# 150226_AriloRX_REV2_0_0.net
KiCad netlist of a schematic drawn in EAGLE
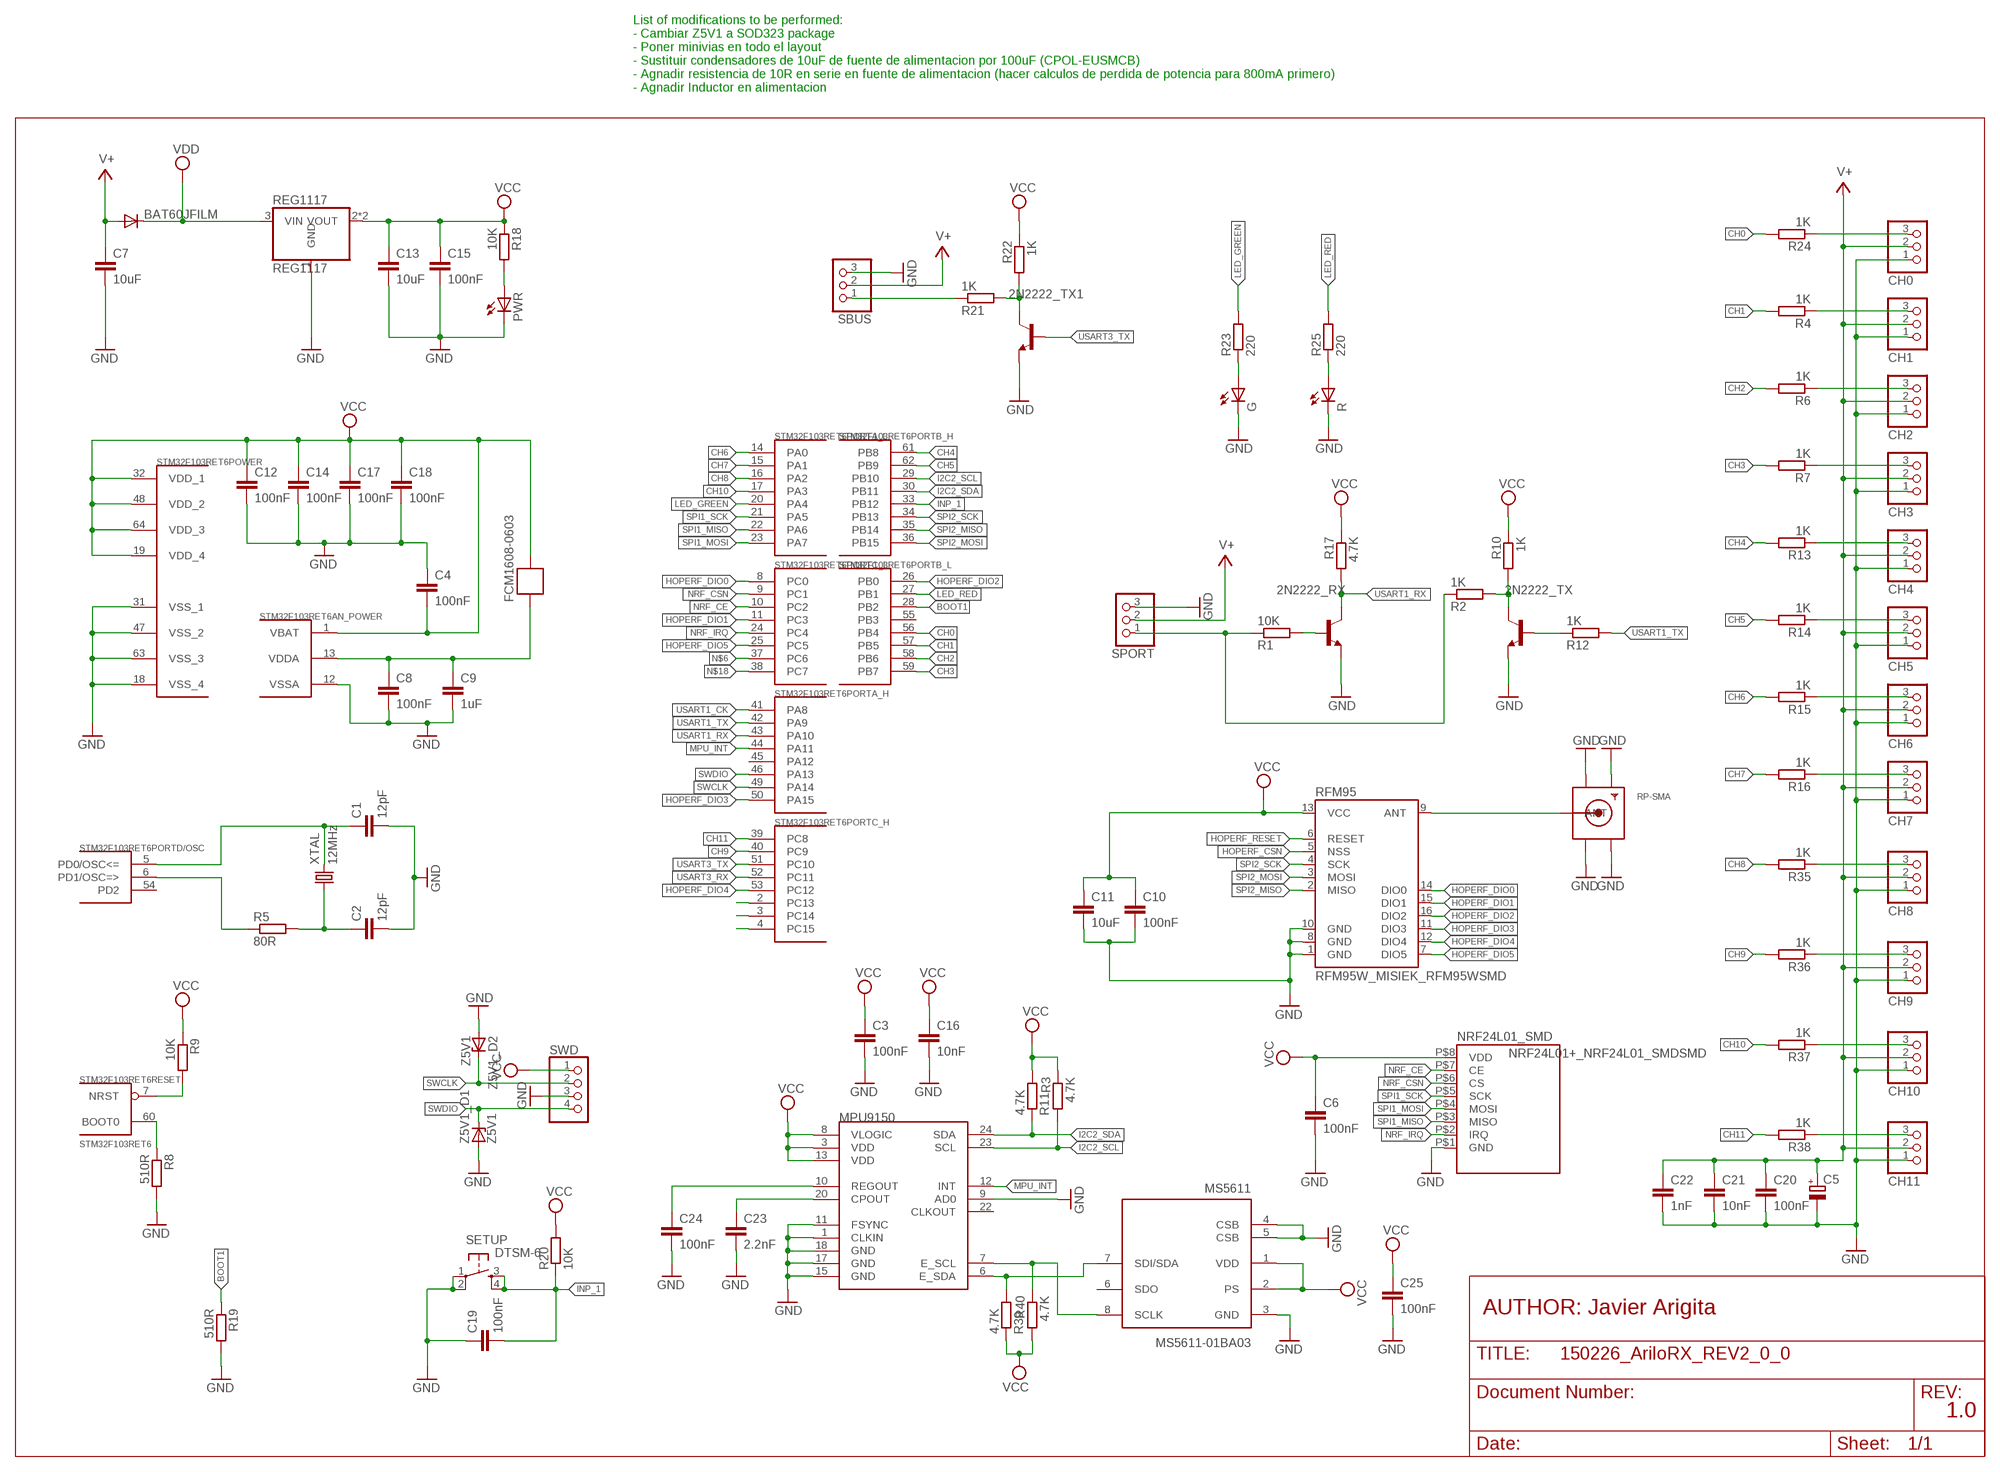
[diagram p0: schematic, sheet 1]

(export (version "E")
  (design (tool "Eeschema 10.0.6"))
  (components
    (comp (ref "2N2222_RX")
      (value "MMBT2222ALT1-NPN-SOT23-BEC")
      (footprint "eagle-import:SOT23-BEC")
      (libsource (lib "eagle-import") (part "-NPN-SOT23-BECMMBT2222ALT1"))
    )
    (comp (ref "2N2222_TX")
      (value "MMBT2222ALT1-NPN-SOT23-BEC")
      (footprint "eagle-import:SOT23-BEC")
      (libsource (lib "eagle-import") (part "-NPN-SOT23-BECMMBT2222ALT1"))
    )
    (comp (ref "2N2222_TX1")
      (value "MMBT2222ALT1-NPN-SOT23-BEC")
      (footprint "eagle-import:SOT23-BEC")
      (libsource (lib "eagle-import") (part "-NPN-SOT23-BECMMBT2222ALT1"))
    )
    (comp (ref "BAT60JFILM")
      (value "DIODE-SOD323-R")
      (footprint "eagle-import:SOD323-R")
      (libsource (lib "eagle-import") (part "DIODE-SOD323-R"))
    )
    (comp (ref "C1")
      (value "12pF")
      (footprint "eagle-import:RESISTOR_C0603")
      (libsource (lib "eagle-import") (part "RESISTOR_C-EUC0603"))
    )
    (comp (ref "C2")
      (value "12pF")
      (footprint "eagle-import:RESISTOR_C0603")
      (libsource (lib "eagle-import") (part "RESISTOR_C-EUC0603"))
    )
    (comp (ref "C3")
      (value "100nF")
      (footprint "eagle-import:RESISTOR_C0603")
      (libsource (lib "eagle-import") (part "RESISTOR_C-EUC0603"))
    )
    (comp (ref "C4")
      (value "100nF")
      (footprint "eagle-import:RESISTOR_C0603")
      (libsource (lib "eagle-import") (part "RESISTOR_C-EUC0603"))
    )
    (comp (ref "C5")
      (value "CPOL-EUSMCB")
      (footprint "eagle-import:SMC_B")
      (libsource (lib "eagle-import") (part "CPOL-EUSMCB"))
    )
    (comp (ref "C6")
      (value "100nF")
      (footprint "eagle-import:RESISTOR_C0603")
      (libsource (lib "eagle-import") (part "RESISTOR_C-EUC0603"))
    )
    (comp (ref "C7")
      (value "10uF")
      (footprint "eagle-import:RESISTOR_C3216")
      (libsource (lib "eagle-import") (part "RESISTOR_C-EUC3216"))
    )
    (comp (ref "C8")
      (value "100nF")
      (footprint "eagle-import:RESISTOR_C0603")
      (libsource (lib "eagle-import") (part "RESISTOR_C-EUC0603"))
    )
    (comp (ref "C9")
      (value "1uF")
      (footprint "eagle-import:RESISTOR_C0603")
      (libsource (lib "eagle-import") (part "RESISTOR_C-EUC0603"))
    )
    (comp (ref "C10")
      (value "100nF")
      (footprint "eagle-import:RESISTOR_C0603")
      (libsource (lib "eagle-import") (part "RESISTOR_C-EUC0603"))
    )
    (comp (ref "C11")
      (value "10uF")
      (footprint "eagle-import:RESISTOR_C3216")
      (libsource (lib "eagle-import") (part "RESISTOR_C-EUC3216"))
    )
    (comp (ref "C12")
      (value "100nF")
      (footprint "eagle-import:RESISTOR_C0603")
      (libsource (lib "eagle-import") (part "RESISTOR_C-EUC0603"))
    )
    (comp (ref "C13")
      (value "10uF")
      (footprint "eagle-import:RESISTOR_C3216")
      (libsource (lib "eagle-import") (part "RESISTOR_C-EUC3216"))
    )
    (comp (ref "C14")
      (value "100nF")
      (footprint "eagle-import:RESISTOR_C0603")
      (libsource (lib "eagle-import") (part "RESISTOR_C-EUC0603"))
    )
    (comp (ref "C15")
      (value "100nF")
      (footprint "eagle-import:RESISTOR_C0603")
      (libsource (lib "eagle-import") (part "RESISTOR_C-EUC0603"))
    )
    (comp (ref "C16")
      (value "10nF")
      (footprint "eagle-import:RESISTOR_C0603")
      (libsource (lib "eagle-import") (part "RESISTOR_C-EUC0603"))
    )
    (comp (ref "C17")
      (value "100nF")
      (footprint "eagle-import:RESISTOR_C0603")
      (libsource (lib "eagle-import") (part "RESISTOR_C-EUC0603"))
    )
    (comp (ref "C18")
      (value "100nF")
      (footprint "eagle-import:RESISTOR_C0603")
      (libsource (lib "eagle-import") (part "RESISTOR_C-EUC0603"))
    )
    (comp (ref "C19")
      (value "100nF")
      (footprint "eagle-import:RESISTOR_C0603")
      (libsource (lib "eagle-import") (part "RESISTOR_C-EUC0603"))
    )
    (comp (ref "C20")
      (value "100nF")
      (footprint "eagle-import:RESISTOR_C0603")
      (libsource (lib "eagle-import") (part "RESISTOR_C-EUC0603"))
    )
    (comp (ref "C21")
      (value "10nF")
      (footprint "eagle-import:RESISTOR_C0603")
      (libsource (lib "eagle-import") (part "RESISTOR_C-EUC0603"))
    )
    (comp (ref "C22")
      (value "1nF")
      (footprint "eagle-import:RESISTOR_C0603")
      (libsource (lib "eagle-import") (part "RESISTOR_C-EUC0603"))
    )
    (comp (ref "C23")
      (value "2.2nF")
      (footprint "eagle-import:RESISTOR_C0603")
      (libsource (lib "eagle-import") (part "RESISTOR_C-EUC0603"))
    )
    (comp (ref "C24")
      (value "100nF")
      (footprint "eagle-import:RESISTOR_C0603")
      (libsource (lib "eagle-import") (part "RESISTOR_C-EUC0603"))
    )
    (comp (ref "C25")
      (value "100nF")
      (footprint "eagle-import:RESISTOR_C0603")
      (libsource (lib "eagle-import") (part "RESISTOR_C-EUC0603"))
    )
    (comp (ref "CH0")
      (value "PINHD-1X3")
      (footprint "eagle-import:1X03")
      (libsource (lib "eagle-import") (part "PINHD-1X3"))
    )
    (comp (ref "CH1")
      (value "PINHD-1X3")
      (footprint "eagle-import:1X03")
      (libsource (lib "eagle-import") (part "PINHD-1X3"))
    )
    (comp (ref "CH2")
      (value "PINHD-1X3")
      (footprint "eagle-import:1X03")
      (libsource (lib "eagle-import") (part "PINHD-1X3"))
    )
    (comp (ref "CH3")
      (value "PINHD-1X3")
      (footprint "eagle-import:1X03")
      (libsource (lib "eagle-import") (part "PINHD-1X3"))
    )
    (comp (ref "CH4")
      (value "PINHD-1X3")
      (footprint "eagle-import:1X03")
      (libsource (lib "eagle-import") (part "PINHD-1X3"))
    )
    (comp (ref "CH5")
      (value "PINHD-1X3")
      (footprint "eagle-import:1X03")
      (libsource (lib "eagle-import") (part "PINHD-1X3"))
    )
    (comp (ref "CH6")
      (value "PINHD-1X3")
      (footprint "eagle-import:1X03")
      (libsource (lib "eagle-import") (part "PINHD-1X3"))
    )
    (comp (ref "CH7")
      (value "PINHD-1X3")
      (footprint "eagle-import:1X03")
      (libsource (lib "eagle-import") (part "PINHD-1X3"))
    )
    (comp (ref "CH8")
      (value "PINHD-1X3")
      (footprint "eagle-import:1X03")
      (libsource (lib "eagle-import") (part "PINHD-1X3"))
    )
    (comp (ref "CH9")
      (value "PINHD-1X3")
      (footprint "eagle-import:1X03")
      (libsource (lib "eagle-import") (part "PINHD-1X3"))
    )
    (comp (ref "CH10")
      (value "PINHD-1X3")
      (footprint "eagle-import:1X03")
      (libsource (lib "eagle-import") (part "PINHD-1X3"))
    )
    (comp (ref "CH11")
      (value "PINHD-1X3")
      (footprint "eagle-import:1X03")
      (libsource (lib "eagle-import") (part "PINHD-1X3"))
    )
    (comp (ref "FCM1608-0603")
      (value "FERRITE-BEAD")
      (footprint "eagle-import:R0603")
      (libsource (lib "eagle-import") (part "FERRITE-BEAD"))
    )
    (comp (ref "G")
      (value "LEDCHIP-LED0603")
      (footprint "eagle-import:CHIP-LED0603")
      (libsource (lib "eagle-import") (part "LEDCHIP-LED0603"))
    )
    (comp (ref "MPU9150")
      (value "MPU-9150QFN-24-NP")
      (footprint "eagle-import:QFN-24-NP")
      (libsource (lib "eagle-import") (part "MPU-9150QFN-24-NP"))
    )
    (comp (ref "MS5611")
      (value "MS5611-01BA03")
      (footprint "eagle-import:SON125P300X500X100-8N")
      (libsource (lib "eagle-import") (part "MS5611-01BA03"))
    )
    (comp (ref "NRF24L01_SMD")
      (value "NRF24L01+_NRF24L01_SMDSMD")
      (footprint "eagle-import:NRF24L01+_NRF24L01_SMD")
      (libsource (lib "eagle-import") (part "NRF24L01+_NRF24L01_SMDSMD"))
    )
    (comp (ref "PWR")
      (value "LED_LEDCHIP-LED0603")
      (footprint "eagle-import:LED_CHIP-LED0603")
      (libsource (lib "eagle-import") (part "LED_LEDCHIP-LED0603"))
    )
    (comp (ref "R")
      (value "LEDCHIP-LED0603")
      (footprint "eagle-import:CHIP-LED0603")
      (libsource (lib "eagle-import") (part "LEDCHIP-LED0603"))
    )
    (comp (ref "R1")
      (value "10K")
      (footprint "eagle-import:RCL_R0603")
      (libsource (lib "eagle-import") (part "RCL_R-EU_R0603"))
    )
    (comp (ref "R2")
      (value "1K")
      (footprint "eagle-import:RCL_R0603")
      (libsource (lib "eagle-import") (part "RCL_R-EU_R0603"))
    )
    (comp (ref "R3")
      (value "4.7K")
      (footprint "eagle-import:RCL_R0603")
      (libsource (lib "eagle-import") (part "RCL_R-EU_R0603"))
    )
    (comp (ref "R4")
      (value "1K")
      (footprint "eagle-import:RCL_R0603")
      (libsource (lib "eagle-import") (part "RCL_R-EU_R0603"))
    )
    (comp (ref "R5")
      (value "80R")
      (footprint "eagle-import:RCL_R0603")
      (libsource (lib "eagle-import") (part "RCL_R-EU_R0603"))
    )
    (comp (ref "R6")
      (value "1K")
      (footprint "eagle-import:RCL_R0603")
      (libsource (lib "eagle-import") (part "RCL_R-EU_R0603"))
    )
    (comp (ref "R7")
      (value "1K")
      (footprint "eagle-import:RCL_R0603")
      (libsource (lib "eagle-import") (part "RCL_R-EU_R0603"))
    )
    (comp (ref "R8")
      (value "510R")
      (footprint "eagle-import:RCL_R0603")
      (libsource (lib "eagle-import") (part "RCL_R-EU_R0603"))
    )
    (comp (ref "R9")
      (value "10K")
      (footprint "eagle-import:RCL_R0603")
      (libsource (lib "eagle-import") (part "RCL_R-EU_R0603"))
    )
    (comp (ref "R10")
      (value "1K")
      (footprint "eagle-import:RCL_R0603")
      (libsource (lib "eagle-import") (part "RCL_R-EU_R0603"))
    )
    (comp (ref "R11")
      (value "4.7K")
      (footprint "eagle-import:RCL_R0603")
      (libsource (lib "eagle-import") (part "RCL_R-EU_R0603"))
    )
    (comp (ref "R12")
      (value "1K")
      (footprint "eagle-import:RCL_R0603")
      (libsource (lib "eagle-import") (part "RCL_R-EU_R0603"))
    )
    (comp (ref "R13")
      (value "1K")
      (footprint "eagle-import:RCL_R0603")
      (libsource (lib "eagle-import") (part "RCL_R-EU_R0603"))
    )
    (comp (ref "R14")
      (value "1K")
      (footprint "eagle-import:RCL_R0603")
      (libsource (lib "eagle-import") (part "RCL_R-EU_R0603"))
    )
    (comp (ref "R15")
      (value "1K")
      (footprint "eagle-import:RCL_R0603")
      (libsource (lib "eagle-import") (part "RCL_R-EU_R0603"))
    )
    (comp (ref "R16")
      (value "1K")
      (footprint "eagle-import:RCL_R0603")
      (libsource (lib "eagle-import") (part "RCL_R-EU_R0603"))
    )
    (comp (ref "R17")
      (value "4.7K")
      (footprint "eagle-import:RCL_R0603")
      (libsource (lib "eagle-import") (part "RCL_R-EU_R0603"))
    )
    (comp (ref "R18")
      (value "10K")
      (footprint "eagle-import:RCL_R0603")
      (libsource (lib "eagle-import") (part "RCL_R-EU_R0603"))
    )
    (comp (ref "R19")
      (value "510R")
      (footprint "eagle-import:RCL_R0603")
      (libsource (lib "eagle-import") (part "RCL_R-EU_R0603"))
    )
    (comp (ref "R20")
      (value "10K")
      (footprint "eagle-import:RCL_R0603")
      (libsource (lib "eagle-import") (part "RCL_R-EU_R0603"))
    )
    (comp (ref "R21")
      (value "1K")
      (footprint "eagle-import:RCL_R0603")
      (libsource (lib "eagle-import") (part "RCL_R-EU_R0603"))
    )
    (comp (ref "R22")
      (value "1K")
      (footprint "eagle-import:RCL_R0603")
      (libsource (lib "eagle-import") (part "RCL_R-EU_R0603"))
    )
    (comp (ref "R23")
      (value "220")
      (footprint "eagle-import:RCL_R0603")
      (libsource (lib "eagle-import") (part "RCL_R-EU_R0603"))
    )
    (comp (ref "R24")
      (value "1K")
      (footprint "eagle-import:RCL_R0603")
      (libsource (lib "eagle-import") (part "RCL_R-EU_R0603"))
    )
    (comp (ref "R25")
      (value "220")
      (footprint "eagle-import:RCL_R0603")
      (libsource (lib "eagle-import") (part "RCL_R-EU_R0603"))
    )
    (comp (ref "R35")
      (value "1K")
      (footprint "eagle-import:RCL_R0603")
      (libsource (lib "eagle-import") (part "RCL_R-EU_R0603"))
    )
    (comp (ref "R36")
      (value "1K")
      (footprint "eagle-import:RCL_R0603")
      (libsource (lib "eagle-import") (part "RCL_R-EU_R0603"))
    )
    (comp (ref "R37")
      (value "1K")
      (footprint "eagle-import:RCL_R0603")
      (libsource (lib "eagle-import") (part "RCL_R-EU_R0603"))
    )
    (comp (ref "R38")
      (value "1K")
      (footprint "eagle-import:RCL_R0603")
      (libsource (lib "eagle-import") (part "RCL_R-EU_R0603"))
    )
    (comp (ref "R39")
      (value "4.7K")
      (footprint "eagle-import:RCL_R0603")
      (libsource (lib "eagle-import") (part "RCL_R-EU_R0603"))
    )
    (comp (ref "R40")
      (value "4.7K")
      (footprint "eagle-import:RCL_R0603")
      (libsource (lib "eagle-import") (part "RCL_R-EU_R0603"))
    )
    (comp (ref "REG1117")
      (value "REG1117")
      (footprint "eagle-import:SOT223")
      (libsource (lib "eagle-import") (part "REG1117"))
    )
    (comp (ref "RFM95")
      (value "RFM95W_MISIEK_RFM95WSMD")
      (footprint "eagle-import:RFM95W_MISIEK_RFM95W_SMD")
      (libsource (lib "eagle-import") (part "RFM95W_MISIEK_RFM95WSMD"))
    )
    (comp (ref "RP-SMA")
      (value "SMACONNECTOR_EDGE")
      (footprint "eagle-import:SMA_EDGELAUNCH")
      (libsource (lib "eagle-import") (part "SMACONNECTOR_EDGE"))
    )
    (comp (ref "SBUS")
      (value "PINHD-1X3")
      (footprint "eagle-import:1X03")
      (libsource (lib "eagle-import") (part "PINHD-1X3"))
    )
    (comp (ref "SETUP")
      (value "DTSM-6")
      (footprint "eagle-import:DTSM-6")
      (libsource (lib "eagle-import") (part "DTSM-6"))
    )
    (comp (ref "SPORT")
      (value "PINHD-1X3")
      (footprint "eagle-import:1X03")
      (libsource (lib "eagle-import") (part "PINHD-1X3"))
    )
    (comp (ref "STM32F103RET6")
      (value "STM32F103RET6")
      (footprint "eagle-import:TQFP64")
      (libsource (lib "eagle-import") (part "STM32F10XRXT6"))
    )
    (comp (ref "SWD")
      (value "PINHD-1X4")
      (footprint "eagle-import:1X04")
      (libsource (lib "eagle-import") (part "PINHD-1X4"))
    )
    (comp (ref "XTAL")
      (value "12MHz")
      (footprint "eagle-import:CRYSTAL-SMD-5X3")
      (libsource (lib "eagle-import") (part "CRYSTAL5X3"))
    )
    (comp (ref "Z5V1_D1")
      (value "Z5V1")
      (footprint "eagle-import:SOD80C")
      (libsource (lib "eagle-import") (part "ZENER-DIODESOD80C"))
    )
    (comp (ref "Z5V1_D2")
      (value "Z5V1")
      (footprint "eagle-import:SOD80C")
      (libsource (lib "eagle-import") (part "ZENER-DIODESOD80C"))
    )
  )
  (nets
    (net (code "1") (name "BOOT1") (class "Default")
      (node (ref "R19") (pin "1") (pinfunction "1_1") (pintype "passive"))
      (node (ref "STM32F103RET6") (pin "28") (pinfunction "PB2_28") (pintype "bidirectional"))
    )
    (net (code "2") (name "CH0") (class "Default")
      (node (ref "R24") (pin "2") (pinfunction "2_2") (pintype "passive"))
      (node (ref "STM32F103RET6") (pin "56") (pinfunction "PB4_56") (pintype "bidirectional"))
    )
    (net (code "3") (name "CH1") (class "Default")
      (node (ref "R4") (pin "2") (pinfunction "2_2") (pintype "passive"))
      (node (ref "STM32F103RET6") (pin "57") (pinfunction "PB5_57") (pintype "bidirectional"))
    )
    (net (code "4") (name "CH2") (class "Default")
      (node (ref "R6") (pin "2") (pinfunction "2_2") (pintype "passive"))
      (node (ref "STM32F103RET6") (pin "58") (pinfunction "PB6_58") (pintype "bidirectional"))
    )
    (net (code "5") (name "CH3") (class "Default")
      (node (ref "R7") (pin "2") (pinfunction "2_2") (pintype "passive"))
      (node (ref "STM32F103RET6") (pin "59") (pinfunction "PB7_59") (pintype "bidirectional"))
    )
    (net (code "6") (name "CH4") (class "Default")
      (node (ref "R13") (pin "2") (pinfunction "2_2") (pintype "passive"))
      (node (ref "STM32F103RET6") (pin "61") (pinfunction "PB8_61") (pintype "bidirectional"))
    )
    (net (code "7") (name "CH5") (class "Default")
      (node (ref "R14") (pin "2") (pinfunction "2_2") (pintype "passive"))
      (node (ref "STM32F103RET6") (pin "62") (pinfunction "PB9_62") (pintype "bidirectional"))
    )
    (net (code "8") (name "CH6") (class "Default")
      (node (ref "R15") (pin "2") (pinfunction "2_2") (pintype "passive"))
      (node (ref "STM32F103RET6") (pin "14") (pinfunction "PA0_14") (pintype "bidirectional"))
    )
    (net (code "9") (name "CH7") (class "Default")
      (node (ref "R16") (pin "2") (pinfunction "2_2") (pintype "passive"))
      (node (ref "STM32F103RET6") (pin "15") (pinfunction "PA1_15") (pintype "bidirectional"))
    )
    (net (code "10") (name "CH8") (class "Default")
      (node (ref "R35") (pin "2") (pinfunction "2_2") (pintype "passive"))
      (node (ref "STM32F103RET6") (pin "16") (pinfunction "PA2_16") (pintype "bidirectional"))
    )
    (net (code "11") (name "CH9") (class "Default")
      (node (ref "R36") (pin "2") (pinfunction "2_2") (pintype "passive"))
      (node (ref "STM32F103RET6") (pin "40") (pinfunction "PC9_40") (pintype "bidirectional"))
    )
    (net (code "12") (name "CH10") (class "Default")
      (node (ref "R37") (pin "2") (pinfunction "2_2") (pintype "passive"))
      (node (ref "STM32F103RET6") (pin "17") (pinfunction "PA3_17") (pintype "bidirectional"))
    )
    (net (code "13") (name "CH11") (class "Default")
      (node (ref "R38") (pin "2") (pinfunction "2_2") (pintype "passive"))
      (node (ref "STM32F103RET6") (pin "39") (pinfunction "PC8_39") (pintype "bidirectional"))
    )
    (net (code "14") (name "GND") (class "Default")
      (node (ref "2N2222_RX") (pin "E") (pinfunction "E_E") (pintype "passive"))
      (node (ref "2N2222_TX") (pin "E") (pinfunction "E_E") (pintype "passive"))
      (node (ref "2N2222_TX1") (pin "E") (pinfunction "E_E") (pintype "passive"))
      (node (ref "C1") (pin "2") (pinfunction "2_2") (pintype "passive"))
      (node (ref "C10") (pin "2") (pinfunction "2_2") (pintype "passive"))
      (node (ref "C11") (pin "2") (pinfunction "2_2") (pintype "passive"))
      (node (ref "C12") (pin "2") (pinfunction "2_2") (pintype "passive"))
      (node (ref "C13") (pin "2") (pinfunction "2_2") (pintype "passive"))
      (node (ref "C14") (pin "2") (pinfunction "2_2") (pintype "passive"))
      (node (ref "C15") (pin "2") (pinfunction "2_2") (pintype "passive"))
      (node (ref "C16") (pin "2") (pinfunction "2_2") (pintype "passive"))
      (node (ref "C17") (pin "2") (pinfunction "2_2") (pintype "passive"))
      (node (ref "C18") (pin "2") (pinfunction "2_2") (pintype "passive"))
      (node (ref "C19") (pin "1") (pinfunction "1_1") (pintype "passive"))
      (node (ref "C2") (pin "2") (pinfunction "2_2") (pintype "passive"))
      (node (ref "C20") (pin "2") (pinfunction "2_2") (pintype "passive"))
      (node (ref "C21") (pin "2") (pinfunction "2_2") (pintype "passive"))
      (node (ref "C22") (pin "2") (pinfunction "2_2") (pintype "passive"))
      (node (ref "C23") (pin "2") (pinfunction "2_2") (pintype "passive"))
      (node (ref "C24") (pin "2") (pinfunction "2_2") (pintype "passive"))
      (node (ref "C25") (pin "2") (pinfunction "2_2") (pintype "passive"))
      (node (ref "C3") (pin "2") (pinfunction "2_2") (pintype "passive"))
      (node (ref "C4") (pin "1") (pinfunction "1_1") (pintype "passive"))
      (node (ref "C5") (pin "-") (pinfunction "-_-") (pintype "passive"))
      (node (ref "C6") (pin "2") (pinfunction "2_2") (pintype "passive"))
      (node (ref "C7") (pin "2") (pinfunction "2_2") (pintype "passive"))
      (node (ref "C8") (pin "2") (pinfunction "2_2") (pintype "passive"))
      (node (ref "C9") (pin "2") (pinfunction "2_2") (pintype "passive"))
      (node (ref "CH0") (pin "1") (pinfunction "1_1") (pintype "passive"))
      (node (ref "CH1") (pin "1") (pinfunction "1_1") (pintype "passive"))
      (node (ref "CH10") (pin "1") (pinfunction "1_1") (pintype "passive"))
      (node (ref "CH11") (pin "1") (pinfunction "1_1") (pintype "passive"))
      (node (ref "CH2") (pin "1") (pinfunction "1_1") (pintype "passive"))
      (node (ref "CH3") (pin "1") (pinfunction "1_1") (pintype "passive"))
      (node (ref "CH4") (pin "1") (pinfunction "1_1") (pintype "passive"))
      (node (ref "CH5") (pin "1") (pinfunction "1_1") (pintype "passive"))
      (node (ref "CH6") (pin "1") (pinfunction "1_1") (pintype "passive"))
      (node (ref "CH7") (pin "1") (pinfunction "1_1") (pintype "passive"))
      (node (ref "CH8") (pin "1") (pinfunction "1_1") (pintype "passive"))
      (node (ref "CH9") (pin "1") (pinfunction "1_1") (pintype "passive"))
      (node (ref "G") (pin "C") (pinfunction "C_C") (pintype "passive"))
      (node (ref "MPU9150") (pin "1") (pinfunction "CLKIN_1") (pintype "bidirectional"))
      (node (ref "MPU9150") (pin "11") (pinfunction "FSYNC_11") (pintype "bidirectional"))
      (node (ref "MPU9150") (pin "15") (pinfunction "GND_15") (pintype "bidirectional"))
      (node (ref "MPU9150") (pin "17") (pinfunction "GND_17") (pintype "bidirectional"))
      (node (ref "MPU9150") (pin "18") (pinfunction "GND_18") (pintype "bidirectional"))
      (node (ref "MPU9150") (pin "9") (pinfunction "AD0_9") (pintype "bidirectional"))
      (node (ref "MS5611") (pin "3") (pinfunction "GND_3") (pintype "power_in"))
      (node (ref "MS5611") (pin "4") (pinfunction "CSB_4") (pintype "input"))
      (node (ref "MS5611") (pin "5") (pinfunction "CSB_5") (pintype "input"))
      (node (ref "NRF24L01_SMD") (pin "P$1") (pinfunction "GND_P$1") (pintype "power_in"))
      (node (ref "PWR") (pin "C") (pinfunction "C_C") (pintype "passive"))
      (node (ref "R") (pin "C") (pinfunction "C_C") (pintype "passive"))
      (node (ref "R19") (pin "2") (pinfunction "2_2") (pintype "passive"))
      (node (ref "R8") (pin "2") (pinfunction "2_2") (pintype "passive"))
      (node (ref "REG1117") (pin "1") (pinfunction "GND_1") (pintype "power_in"))
      (node (ref "RFM95") (pin "1") (pinfunction "GND_1") (pintype "power_in"))
      (node (ref "RFM95") (pin "10") (pinfunction "GND_10") (pintype "power_in"))
      (node (ref "RFM95") (pin "8") (pinfunction "GND_8") (pintype "power_in"))
      (node (ref "RP-SMA") (pin "GND@1") (pinfunction "GND4_GND@1") (pintype "power_in"))
      (node (ref "RP-SMA") (pin "GND@2") (pinfunction "GND3_GND@2") (pintype "power_in"))
      (node (ref "RP-SMA") (pin "GND@3") (pinfunction "GND2_GND@3") (pintype "power_in"))
      (node (ref "RP-SMA") (pin "GND@4") (pinfunction "GND1_GND@4") (pintype "power_in"))
      (node (ref "SBUS") (pin "3") (pinfunction "3_3") (pintype "passive"))
      (node (ref "SETUP") (pin "1") (pinfunction "1_1") (pintype "passive"))
      (node (ref "SETUP") (pin "2") (pinfunction "2_2") (pintype "passive"))
      (node (ref "SPORT") (pin "3") (pinfunction "3_3") (pintype "passive"))
      (node (ref "STM32F103RET6") (pin "12") (pinfunction "VSSA_12") (pintype "power_in"))
      (node (ref "STM32F103RET6") (pin "18") (pinfunction "VSS_4_18") (pintype "power_in"))
      (node (ref "STM32F103RET6") (pin "31") (pinfunction "VSS_1_31") (pintype "power_in"))
      (node (ref "STM32F103RET6") (pin "47") (pinfunction "VSS_2_47") (pintype "power_in"))
      (node (ref "STM32F103RET6") (pin "63") (pinfunction "VSS_3_63") (pintype "power_in"))
      (node (ref "SWD") (pin "3") (pinfunction "3_3") (pintype "passive"))
      (node (ref "Z5V1_D1") (pin "A") (pinfunction "A_A") (pintype "passive"))
      (node (ref "Z5V1_D2") (pin "A") (pinfunction "A_A") (pintype "passive"))
    )
    (net (code "15") (name "HOPERF_CSN") (class "Default")
      (node (ref "RFM95") (pin "5") (pinfunction "NSS_5") (pintype "input"))
    )
    (net (code "16") (name "HOPERF_DIO0") (class "Default")
      (node (ref "RFM95") (pin "14") (pinfunction "DIO0_14") (pintype "input"))
      (node (ref "STM32F103RET6") (pin "8") (pinfunction "PC0_8") (pintype "bidirectional"))
    )
    (net (code "17") (name "HOPERF_DIO1") (class "Default")
      (node (ref "RFM95") (pin "15") (pinfunction "DIO1_15") (pintype "input"))
      (node (ref "STM32F103RET6") (pin "11") (pinfunction "PC3_11") (pintype "bidirectional"))
    )
    (net (code "18") (name "HOPERF_DIO2") (class "Default")
      (node (ref "RFM95") (pin "16") (pinfunction "DIO2_16") (pintype "input"))
      (node (ref "STM32F103RET6") (pin "26") (pinfunction "PB0_26") (pintype "bidirectional"))
    )
    (net (code "19") (name "HOPERF_DIO3") (class "Default")
      (node (ref "RFM95") (pin "11") (pinfunction "DIO3_11") (pintype "bidirectional"))
      (node (ref "STM32F103RET6") (pin "50") (pinfunction "PA15_50") (pintype "bidirectional"))
    )
    (net (code "20") (name "HOPERF_DIO4") (class "Default")
      (node (ref "RFM95") (pin "12") (pinfunction "DIO4_12") (pintype "bidirectional"))
      (node (ref "STM32F103RET6") (pin "53") (pinfunction "PC12_53") (pintype "bidirectional"))
    )
    (net (code "21") (name "HOPERF_DIO5") (class "Default")
      (node (ref "RFM95") (pin "7") (pinfunction "DIO5_7") (pintype "bidirectional"))
      (node (ref "STM32F103RET6") (pin "25") (pinfunction "PC5_25") (pintype "bidirectional"))
    )
    (net (code "22") (name "HOPERF_RESET") (class "Default")
      (node (ref "RFM95") (pin "6") (pinfunction "RESET_6") (pintype "output"))
    )
    (net (code "23") (name "I2C2_SCL") (class "Default")
      (node (ref "MPU9150") (pin "23") (pinfunction "SCL_23") (pintype "bidirectional"))
      (node (ref "R3") (pin "2") (pinfunction "2_2") (pintype "passive"))
      (node (ref "STM32F103RET6") (pin "29") (pinfunction "PB10_29") (pintype "bidirectional"))
    )
    (net (code "24") (name "I2C2_SDA") (class "Default")
      (node (ref "MPU9150") (pin "24") (pinfunction "SDA_24") (pintype "bidirectional"))
      (node (ref "R11") (pin "1") (pinfunction "1_1") (pintype "passive"))
      (node (ref "STM32F103RET6") (pin "30") (pinfunction "PB11_30") (pintype "bidirectional"))
    )
    (net (code "25") (name "INP_1") (class "Default")
      (node (ref "C19") (pin "2") (pinfunction "2_2") (pintype "passive"))
      (node (ref "R20") (pin "1") (pinfunction "1_1") (pintype "passive"))
      (node (ref "SETUP") (pin "3") (pinfunction "3_3") (pintype "passive"))
      (node (ref "SETUP") (pin "4") (pinfunction "4_4") (pintype "passive"))
      (node (ref "STM32F103RET6") (pin "33") (pinfunction "PB12_33") (pintype "bidirectional"))
    )
    (net (code "26") (name "LED_GREEN") (class "Default")
      (node (ref "R23") (pin "2") (pinfunction "2_2") (pintype "passive"))
      (node (ref "STM32F103RET6") (pin "20") (pinfunction "PA4_20") (pintype "bidirectional"))
    )
    (net (code "27") (name "LED_RED") (class "Default")
      (node (ref "R25") (pin "2") (pinfunction "2_2") (pintype "passive"))
      (node (ref "STM32F103RET6") (pin "27") (pinfunction "PB1_27") (pintype "bidirectional"))
    )
    (net (code "28") (name "MPU_INT") (class "Default")
      (node (ref "MPU9150") (pin "12") (pinfunction "INT_12") (pintype "bidirectional"))
      (node (ref "STM32F103RET6") (pin "44") (pinfunction "PA11_44") (pintype "bidirectional"))
    )
    (net (code "29") (name "N$6") (class "Default")
      (node (ref "STM32F103RET6") (pin "37") (pinfunction "PC6_37") (pintype "bidirectional"))
    )
    (net (code "30") (name "N$18") (class "Default")
      (node (ref "STM32F103RET6") (pin "38") (pinfunction "PC7_38") (pintype "bidirectional"))
    )
    (net (code "31") (name "NRF_CE") (class "Default")
      (node (ref "NRF24L01_SMD") (pin "P$7") (pinfunction "CE_P$7") (pintype "input"))
      (node (ref "STM32F103RET6") (pin "10") (pinfunction "PC2_10") (pintype "bidirectional"))
    )
    (net (code "32") (name "NRF_CSN") (class "Default")
      (node (ref "NRF24L01_SMD") (pin "P$6") (pinfunction "CS_P$6") (pintype "input"))
      (node (ref "STM32F103RET6") (pin "9") (pinfunction "PC1_9") (pintype "bidirectional"))
    )
    (net (code "33") (name "NRF_IRQ") (class "Default")
      (node (ref "NRF24L01_SMD") (pin "P$2") (pinfunction "IRQ_P$2") (pintype "output"))
      (node (ref "STM32F103RET6") (pin "24") (pinfunction "PC4_24") (pintype "bidirectional"))
    )
    (net (code "34") (name "Net-(2N2222_RX-PadB)") (class "Default")
      (node (ref "2N2222_RX") (pin "B") (pinfunction "B_B") (pintype "passive"))
      (node (ref "R1") (pin "2") (pinfunction "2_2") (pintype "passive"))
    )
    (net (code "35") (name "Net-(2N2222_TX-PadB)") (class "Default")
      (node (ref "2N2222_TX") (pin "B") (pinfunction "B_B") (pintype "passive"))
      (node (ref "R12") (pin "1") (pinfunction "1_1") (pintype "passive"))
    )
    (net (code "36") (name "Net-(2N2222_TX-PadC)") (class "Default")
      (node (ref "2N2222_TX") (pin "C") (pinfunction "C_C") (pintype "passive"))
      (node (ref "R10") (pin "2") (pinfunction "2_2") (pintype "passive"))
      (node (ref "R2") (pin "2") (pinfunction "2_2") (pintype "passive"))
    )
    (net (code "37") (name "Net-(2N2222_TX1-PadC)") (class "Default")
      (node (ref "2N2222_TX1") (pin "C") (pinfunction "C_C") (pintype "passive"))
      (node (ref "R21") (pin "2") (pinfunction "2_2") (pintype "passive"))
      (node (ref "R22") (pin "2") (pinfunction "2_2") (pintype "passive"))
    )
    (net (code "38") (name "Net-(C2-Pad1)") (class "Default")
      (node (ref "C2") (pin "1") (pinfunction "1_1") (pintype "passive"))
      (node (ref "R5") (pin "2") (pinfunction "2_2") (pintype "passive"))
      (node (ref "XTAL") (pin "1") (pinfunction "1_1") (pintype "passive"))
    )
    (net (code "39") (name "Net-(CH0-Pad3)") (class "Default")
      (node (ref "CH0") (pin "3") (pinfunction "3_3") (pintype "passive"))
      (node (ref "R24") (pin "1") (pinfunction "1_1") (pintype "passive"))
    )
    (net (code "40") (name "Net-(CH1-Pad3)") (class "Default")
      (node (ref "CH1") (pin "3") (pinfunction "3_3") (pintype "passive"))
      (node (ref "R4") (pin "1") (pinfunction "1_1") (pintype "passive"))
    )
    (net (code "41") (name "Net-(CH2-Pad3)") (class "Default")
      (node (ref "CH2") (pin "3") (pinfunction "3_3") (pintype "passive"))
      (node (ref "R6") (pin "1") (pinfunction "1_1") (pintype "passive"))
    )
    (net (code "42") (name "Net-(CH3-Pad3)") (class "Default")
      (node (ref "CH3") (pin "3") (pinfunction "3_3") (pintype "passive"))
      (node (ref "R7") (pin "1") (pinfunction "1_1") (pintype "passive"))
    )
    (net (code "43") (name "Net-(CH4-Pad3)") (class "Default")
      (node (ref "CH4") (pin "3") (pinfunction "3_3") (pintype "passive"))
      (node (ref "R13") (pin "1") (pinfunction "1_1") (pintype "passive"))
    )
    (net (code "44") (name "Net-(CH5-Pad3)") (class "Default")
      (node (ref "CH5") (pin "3") (pinfunction "3_3") (pintype "passive"))
      (node (ref "R14") (pin "1") (pinfunction "1_1") (pintype "passive"))
    )
    (net (code "45") (name "Net-(CH6-Pad3)") (class "Default")
      (node (ref "CH6") (pin "3") (pinfunction "3_3") (pintype "passive"))
      (node (ref "R15") (pin "1") (pinfunction "1_1") (pintype "passive"))
    )
    (net (code "46") (name "Net-(CH7-Pad3)") (class "Default")
      (node (ref "CH7") (pin "3") (pinfunction "3_3") (pintype "passive"))
      (node (ref "R16") (pin "1") (pinfunction "1_1") (pintype "passive"))
    )
    (net (code "47") (name "Net-(CH8-Pad3)") (class "Default")
      (node (ref "CH8") (pin "3") (pinfunction "3_3") (pintype "passive"))
      (node (ref "R35") (pin "1") (pinfunction "1_1") (pintype "passive"))
    )
    (net (code "48") (name "Net-(CH9-Pad3)") (class "Default")
      (node (ref "CH9") (pin "3") (pinfunction "3_3") (pintype "passive"))
      (node (ref "R36") (pin "1") (pinfunction "1_1") (pintype "passive"))
    )
    (net (code "49") (name "Net-(CH10-Pad3)") (class "Default")
      (node (ref "CH10") (pin "3") (pinfunction "3_3") (pintype "passive"))
      (node (ref "R37") (pin "1") (pinfunction "1_1") (pintype "passive"))
    )
    (net (code "50") (name "Net-(CH11-Pad3)") (class "Default")
      (node (ref "CH11") (pin "3") (pinfunction "3_3") (pintype "passive"))
      (node (ref "R38") (pin "1") (pinfunction "1_1") (pintype "passive"))
    )
    (net (code "51") (name "Net-(FCM1608-0603-P$2)") (class "Default")
      (node (ref "C8") (pin "1") (pinfunction "1_1") (pintype "passive"))
      (node (ref "C9") (pin "1") (pinfunction "1_1") (pintype "passive"))
      (node (ref "FCM1608-0603") (pin "2") (pinfunction "P$2_2") (pintype "bidirectional"))
      (node (ref "STM32F103RET6") (pin "13") (pinfunction "VDDA_13") (pintype "power_in"))
    )
    (net (code "52") (name "Net-(G-PadA)") (class "Default")
      (node (ref "G") (pin "A") (pinfunction "A_A") (pintype "passive"))
      (node (ref "R23") (pin "1") (pinfunction "1_1") (pintype "passive"))
    )
    (net (code "53") (name "Net-(MPU9150-CPOUT)") (class "Default")
      (node (ref "C23") (pin "1") (pinfunction "1_1") (pintype "passive"))
      (node (ref "MPU9150") (pin "20") (pinfunction "CPOUT_20") (pintype "bidirectional"))
    )
    (net (code "54") (name "Net-(MPU9150-E_SCL)") (class "Default")
      (node (ref "MPU9150") (pin "7") (pinfunction "E_SCL_7") (pintype "bidirectional"))
      (node (ref "MS5611") (pin "8") (pinfunction "SCLK_8") (pintype "input"))
      (node (ref "R40") (pin "1") (pinfunction "1_1") (pintype "passive"))
    )
    (net (code "55") (name "Net-(MPU9150-E_SDA)") (class "Default")
      (node (ref "MPU9150") (pin "6") (pinfunction "E_SDA_6") (pintype "bidirectional"))
      (node (ref "MS5611") (pin "7") (pinfunction "SDI/SDA_7") (pintype "bidirectional"))
      (node (ref "R39") (pin "2") (pinfunction "2_2") (pintype "passive"))
    )
    (net (code "56") (name "Net-(MPU9150-REGOUT)") (class "Default")
      (node (ref "C24") (pin "1") (pinfunction "1_1") (pintype "passive"))
      (node (ref "MPU9150") (pin "10") (pinfunction "REGOUT_10") (pintype "bidirectional"))
    )
    (net (code "57") (name "Net-(PWR-PadA)") (class "Default")
      (node (ref "PWR") (pin "A") (pinfunction "A_A") (pintype "passive"))
      (node (ref "R18") (pin "2") (pinfunction "2_2") (pintype "passive"))
    )
    (net (code "58") (name "Net-(R-PadA)") (class "Default")
      (node (ref "R") (pin "A") (pinfunction "A_A") (pintype "passive"))
      (node (ref "R25") (pin "1") (pinfunction "1_1") (pintype "passive"))
    )
    (net (code "59") (name "Net-(R1-Pad1)") (class "Default")
      (node (ref "R1") (pin "1") (pinfunction "1_1") (pintype "passive"))
      (node (ref "R2") (pin "1") (pinfunction "1_1") (pintype "passive"))
      (node (ref "SPORT") (pin "1") (pinfunction "1_1") (pintype "passive"))
    )
    (net (code "60") (name "Net-(R21-Pad1)") (class "Default")
      (node (ref "R21") (pin "1") (pinfunction "1_1") (pintype "passive"))
      (node (ref "SBUS") (pin "1") (pinfunction "1_1") (pintype "passive"))
    )
    (net (code "61") (name "Net-(RFM95-ANT)") (class "Default")
      (node (ref "RFM95") (pin "9") (pinfunction "ANT_9") (pintype "bidirectional"))
      (node (ref "RP-SMA") (pin "P") (pinfunction "ANT_P") (pintype "bidirectional"))
    )
    (net (code "62") (name "Net-(STM32F103RET6H-PD0{slash}OSC<=)") (class "Default")
      (node (ref "C1") (pin "1") (pinfunction "1_1") (pintype "passive"))
      (node (ref "STM32F103RET6") (pin "5") (pinfunction "PD0/OSC<=_5") (pintype "bidirectional"))
      (node (ref "XTAL") (pin "3") (pinfunction "2_3") (pintype "passive"))
    )
    (net (code "63") (name "Net-(STM32F103RET6H-PD1{slash}OSC=>)") (class "Default")
      (node (ref "R5") (pin "1") (pinfunction "1_1") (pintype "passive"))
      (node (ref "STM32F103RET6") (pin "6") (pinfunction "PD1/OSC=>_6") (pintype "bidirectional"))
    )
    (net (code "64") (name "Net-(STM32F103RET6J-BOOT0)") (class "Default")
      (node (ref "R8") (pin "1") (pinfunction "1_1") (pintype "passive"))
      (node (ref "STM32F103RET6") (pin "60") (pinfunction "BOOT0_60") (pintype "input"))
    )
    (net (code "65") (name "Net-(STM32F103RET6J-NRST)") (class "Default")
      (node (ref "R9") (pin "2") (pinfunction "2_2") (pintype "passive"))
      (node (ref "STM32F103RET6") (pin "7") (pinfunction "NRST_7") (pintype "input"))
    )
    (net (code "66") (name "SPI1_MISO") (class "Default")
      (node (ref "NRF24L01_SMD") (pin "P$3") (pinfunction "MISO_P$3") (pintype "output"))
      (node (ref "STM32F103RET6") (pin "22") (pinfunction "PA6_22") (pintype "bidirectional"))
    )
    (net (code "67") (name "SPI1_MOSI") (class "Default")
      (node (ref "NRF24L01_SMD") (pin "P$4") (pinfunction "MOSI_P$4") (pintype "input"))
      (node (ref "STM32F103RET6") (pin "23") (pinfunction "PA7_23") (pintype "bidirectional"))
    )
    (net (code "68") (name "SPI1_SCK") (class "Default")
      (node (ref "NRF24L01_SMD") (pin "P$5") (pinfunction "SCK_P$5") (pintype "input"))
      (node (ref "STM32F103RET6") (pin "21") (pinfunction "PA5_21") (pintype "bidirectional"))
    )
    (net (code "69") (name "SPI2_MISO") (class "Default")
      (node (ref "RFM95") (pin "2") (pinfunction "MISO_2") (pintype "output"))
      (node (ref "STM32F103RET6") (pin "35") (pinfunction "PB14_35") (pintype "bidirectional"))
    )
    (net (code "70") (name "SPI2_MOSI") (class "Default")
      (node (ref "RFM95") (pin "3") (pinfunction "MOSI_3") (pintype "input"))
      (node (ref "STM32F103RET6") (pin "36") (pinfunction "PB15_36") (pintype "bidirectional"))
    )
    (net (code "71") (name "SPI2_SCK") (class "Default")
      (node (ref "RFM95") (pin "4") (pinfunction "SCK_4") (pintype "input"))
      (node (ref "STM32F103RET6") (pin "34") (pinfunction "PB13_34") (pintype "bidirectional"))
    )
    (net (code "72") (name "SWCLK") (class "Default")
      (node (ref "STM32F103RET6") (pin "49") (pinfunction "PA14_49") (pintype "bidirectional"))
      (node (ref "SWD") (pin "2") (pinfunction "2_2") (pintype "passive"))
      (node (ref "Z5V1_D2") (pin "C") (pinfunction "C_C") (pintype "passive"))
    )
    (net (code "73") (name "SWDIO") (class "Default")
      (node (ref "STM32F103RET6") (pin "46") (pinfunction "PA13_46") (pintype "bidirectional"))
      (node (ref "SWD") (pin "4") (pinfunction "4_4") (pintype "passive"))
      (node (ref "Z5V1_D1") (pin "C") (pinfunction "C_C") (pintype "passive"))
    )
    (net (code "74") (name "USART1_CK") (class "Default")
      (node (ref "STM32F103RET6") (pin "41") (pinfunction "PA8_41") (pintype "bidirectional"))
    )
    (net (code "75") (name "USART1_RX") (class "Default")
      (node (ref "2N2222_RX") (pin "C") (pinfunction "C_C") (pintype "passive"))
      (node (ref "R17") (pin "2") (pinfunction "2_2") (pintype "passive"))
      (node (ref "STM32F103RET6") (pin "43") (pinfunction "PA10_43") (pintype "bidirectional"))
    )
    (net (code "76") (name "USART1_TX") (class "Default")
      (node (ref "R12") (pin "2") (pinfunction "2_2") (pintype "passive"))
      (node (ref "STM32F103RET6") (pin "42") (pinfunction "PA9_42") (pintype "bidirectional"))
    )
    (net (code "77") (name "USART3_RX") (class "Default")
      (node (ref "STM32F103RET6") (pin "52") (pinfunction "PC11_52") (pintype "bidirectional"))
    )
    (net (code "78") (name "USART3_TX") (class "Default")
      (node (ref "2N2222_TX1") (pin "B") (pinfunction "B_B") (pintype "passive"))
      (node (ref "STM32F103RET6") (pin "51") (pinfunction "PC10_51") (pintype "bidirectional"))
    )
    (net (code "79") (name "V+") (class "Default")
      (node (ref "BAT60JFILM") (pin "A") (pinfunction "A_A") (pintype "passive"))
      (node (ref "C20") (pin "1") (pinfunction "1_1") (pintype "passive"))
      (node (ref "C21") (pin "1") (pinfunction "1_1") (pintype "passive"))
      (node (ref "C22") (pin "1") (pinfunction "1_1") (pintype "passive"))
      (node (ref "C5") (pin "+") (pinfunction "+_+") (pintype "passive"))
      (node (ref "C7") (pin "1") (pinfunction "1_1") (pintype "passive"))
      (node (ref "CH0") (pin "2") (pinfunction "2_2") (pintype "passive"))
      (node (ref "CH1") (pin "2") (pinfunction "2_2") (pintype "passive"))
      (node (ref "CH10") (pin "2") (pinfunction "2_2") (pintype "passive"))
      (node (ref "CH11") (pin "2") (pinfunction "2_2") (pintype "passive"))
      (node (ref "CH2") (pin "2") (pinfunction "2_2") (pintype "passive"))
      (node (ref "CH3") (pin "2") (pinfunction "2_2") (pintype "passive"))
      (node (ref "CH4") (pin "2") (pinfunction "2_2") (pintype "passive"))
      (node (ref "CH5") (pin "2") (pinfunction "2_2") (pintype "passive"))
      (node (ref "CH6") (pin "2") (pinfunction "2_2") (pintype "passive"))
      (node (ref "CH7") (pin "2") (pinfunction "2_2") (pintype "passive"))
      (node (ref "CH8") (pin "2") (pinfunction "2_2") (pintype "passive"))
      (node (ref "CH9") (pin "2") (pinfunction "2_2") (pintype "passive"))
      (node (ref "SBUS") (pin "2") (pinfunction "2_2") (pintype "passive"))
      (node (ref "SPORT") (pin "2") (pinfunction "2_2") (pintype "passive"))
    )
    (net (code "80") (name "VCC") (class "Default")
      (node (ref "C10") (pin "1") (pinfunction "1_1") (pintype "passive"))
      (node (ref "C11") (pin "1") (pinfunction "1_1") (pintype "passive"))
      (node (ref "C12") (pin "1") (pinfunction "1_1") (pintype "passive"))
      (node (ref "C13") (pin "1") (pinfunction "1_1") (pintype "passive"))
      (node (ref "C14") (pin "1") (pinfunction "1_1") (pintype "passive"))
      (node (ref "C15") (pin "1") (pinfunction "1_1") (pintype "passive"))
      (node (ref "C16") (pin "1") (pinfunction "1_1") (pintype "passive"))
      (node (ref "C17") (pin "1") (pinfunction "1_1") (pintype "passive"))
      (node (ref "C18") (pin "1") (pinfunction "1_1") (pintype "passive"))
      (node (ref "C25") (pin "1") (pinfunction "1_1") (pintype "passive"))
      (node (ref "C3") (pin "1") (pinfunction "1_1") (pintype "passive"))
      (node (ref "C4") (pin "2") (pinfunction "2_2") (pintype "passive"))
      (node (ref "C6") (pin "1") (pinfunction "1_1") (pintype "passive"))
      (node (ref "FCM1608-0603") (pin "1") (pinfunction "P$1_1") (pintype "bidirectional"))
      (node (ref "MPU9150") (pin "13") (pinfunction "VDD_13") (pintype "bidirectional"))
      (node (ref "MPU9150") (pin "3") (pinfunction "VDD_3") (pintype "bidirectional"))
      (node (ref "MPU9150") (pin "8") (pinfunction "VLOGIC_8") (pintype "bidirectional"))
      (node (ref "MS5611") (pin "1") (pinfunction "VDD_1") (pintype "power_in"))
      (node (ref "MS5611") (pin "2") (pinfunction "PS_2") (pintype "input"))
      (node (ref "NRF24L01_SMD") (pin "P$8") (pinfunction "VDD_P$8") (pintype "bidirectional"))
      (node (ref "R10") (pin "1") (pinfunction "1_1") (pintype "passive"))
      (node (ref "R11") (pin "2") (pinfunction "2_2") (pintype "passive"))
      (node (ref "R17") (pin "1") (pinfunction "1_1") (pintype "passive"))
      (node (ref "R18") (pin "1") (pinfunction "1_1") (pintype "passive"))
      (node (ref "R20") (pin "2") (pinfunction "2_2") (pintype "passive"))
      (node (ref "R22") (pin "1") (pinfunction "1_1") (pintype "passive"))
      (node (ref "R3") (pin "1") (pinfunction "1_1") (pintype "passive"))
      (node (ref "R39") (pin "1") (pinfunction "1_1") (pintype "passive"))
      (node (ref "R40") (pin "2") (pinfunction "2_2") (pintype "passive"))
      (node (ref "R9") (pin "1") (pinfunction "1_1") (pintype "passive"))
      (node (ref "REG1117") (pin "2") (pinfunction "VOUT_2") (pintype "power_in"))
      (node (ref "REG1117") (pin "4") (pinfunction "VOUT_4") (pintype "power_in"))
      (node (ref "RFM95") (pin "13") (pinfunction "VCC_13") (pintype "bidirectional"))
      (node (ref "STM32F103RET6") (pin "1") (pinfunction "VBAT_1") (pintype "power_in"))
      (node (ref "STM32F103RET6") (pin "19") (pinfunction "VDD_4_19") (pintype "power_in"))
      (node (ref "STM32F103RET6") (pin "32") (pinfunction "VDD_1_32") (pintype "power_in"))
      (node (ref "STM32F103RET6") (pin "48") (pinfunction "VDD_2_48") (pintype "power_in"))
      (node (ref "STM32F103RET6") (pin "64") (pinfunction "VDD_3_64") (pintype "power_in"))
      (node (ref "SWD") (pin "1") (pinfunction "1_1") (pintype "passive"))
    )
    (net (code "81") (name "VDD") (class "Default")
      (node (ref "BAT60JFILM") (pin "C") (pinfunction "C_C") (pintype "passive"))
      (node (ref "REG1117") (pin "3") (pinfunction "VIN_3") (pintype "input"))
    )
    (net (code "82") (name "unconnected-(MPU9150-CLKOUT-Pad22)") (class "Default")
      (node (ref "MPU9150") (pin "22") (pinfunction "CLKOUT_22") (pintype "bidirectional"))
    )
    (net (code "83") (name "unconnected-(MS5611-SDO-Pad6)") (class "Default")
      (node (ref "MS5611") (pin "6") (pinfunction "SDO_6") (pintype "output"))
    )
    (net (code "84") (name "unconnected-(STM32F103RET6B-PA12-Pad45)") (class "Default")
      (node (ref "STM32F103RET6") (pin "45") (pinfunction "PA12_45") (pintype "bidirectional"))
    )
    (net (code "85") (name "unconnected-(STM32F103RET6E-PB3-Pad55)") (class "Default")
      (node (ref "STM32F103RET6") (pin "55") (pinfunction "PB3_55") (pintype "bidirectional"))
    )
    (net (code "86") (name "unconnected-(STM32F103RET6F-PC13-Pad2)") (class "Default")
      (node (ref "STM32F103RET6") (pin "2") (pinfunction "PC13_2") (pintype "bidirectional"))
    )
    (net (code "87") (name "unconnected-(STM32F103RET6F-PC14-Pad3)") (class "Default")
      (node (ref "STM32F103RET6") (pin "3") (pinfunction "PC14_3") (pintype "bidirectional"))
    )
    (net (code "88") (name "unconnected-(STM32F103RET6F-PC15-Pad4)") (class "Default")
      (node (ref "STM32F103RET6") (pin "4") (pinfunction "PC15_4") (pintype "bidirectional"))
    )
    (net (code "89") (name "unconnected-(STM32F103RET6H-PD2-Pad54)") (class "Default")
      (node (ref "STM32F103RET6") (pin "54") (pinfunction "PD2_54") (pintype "bidirectional"))
    )
  )
)
